# MIXR_Processing_-_STM32_DSP_Microcontrol.net
KiCad netlist of a schematic drawn in Altium Designer
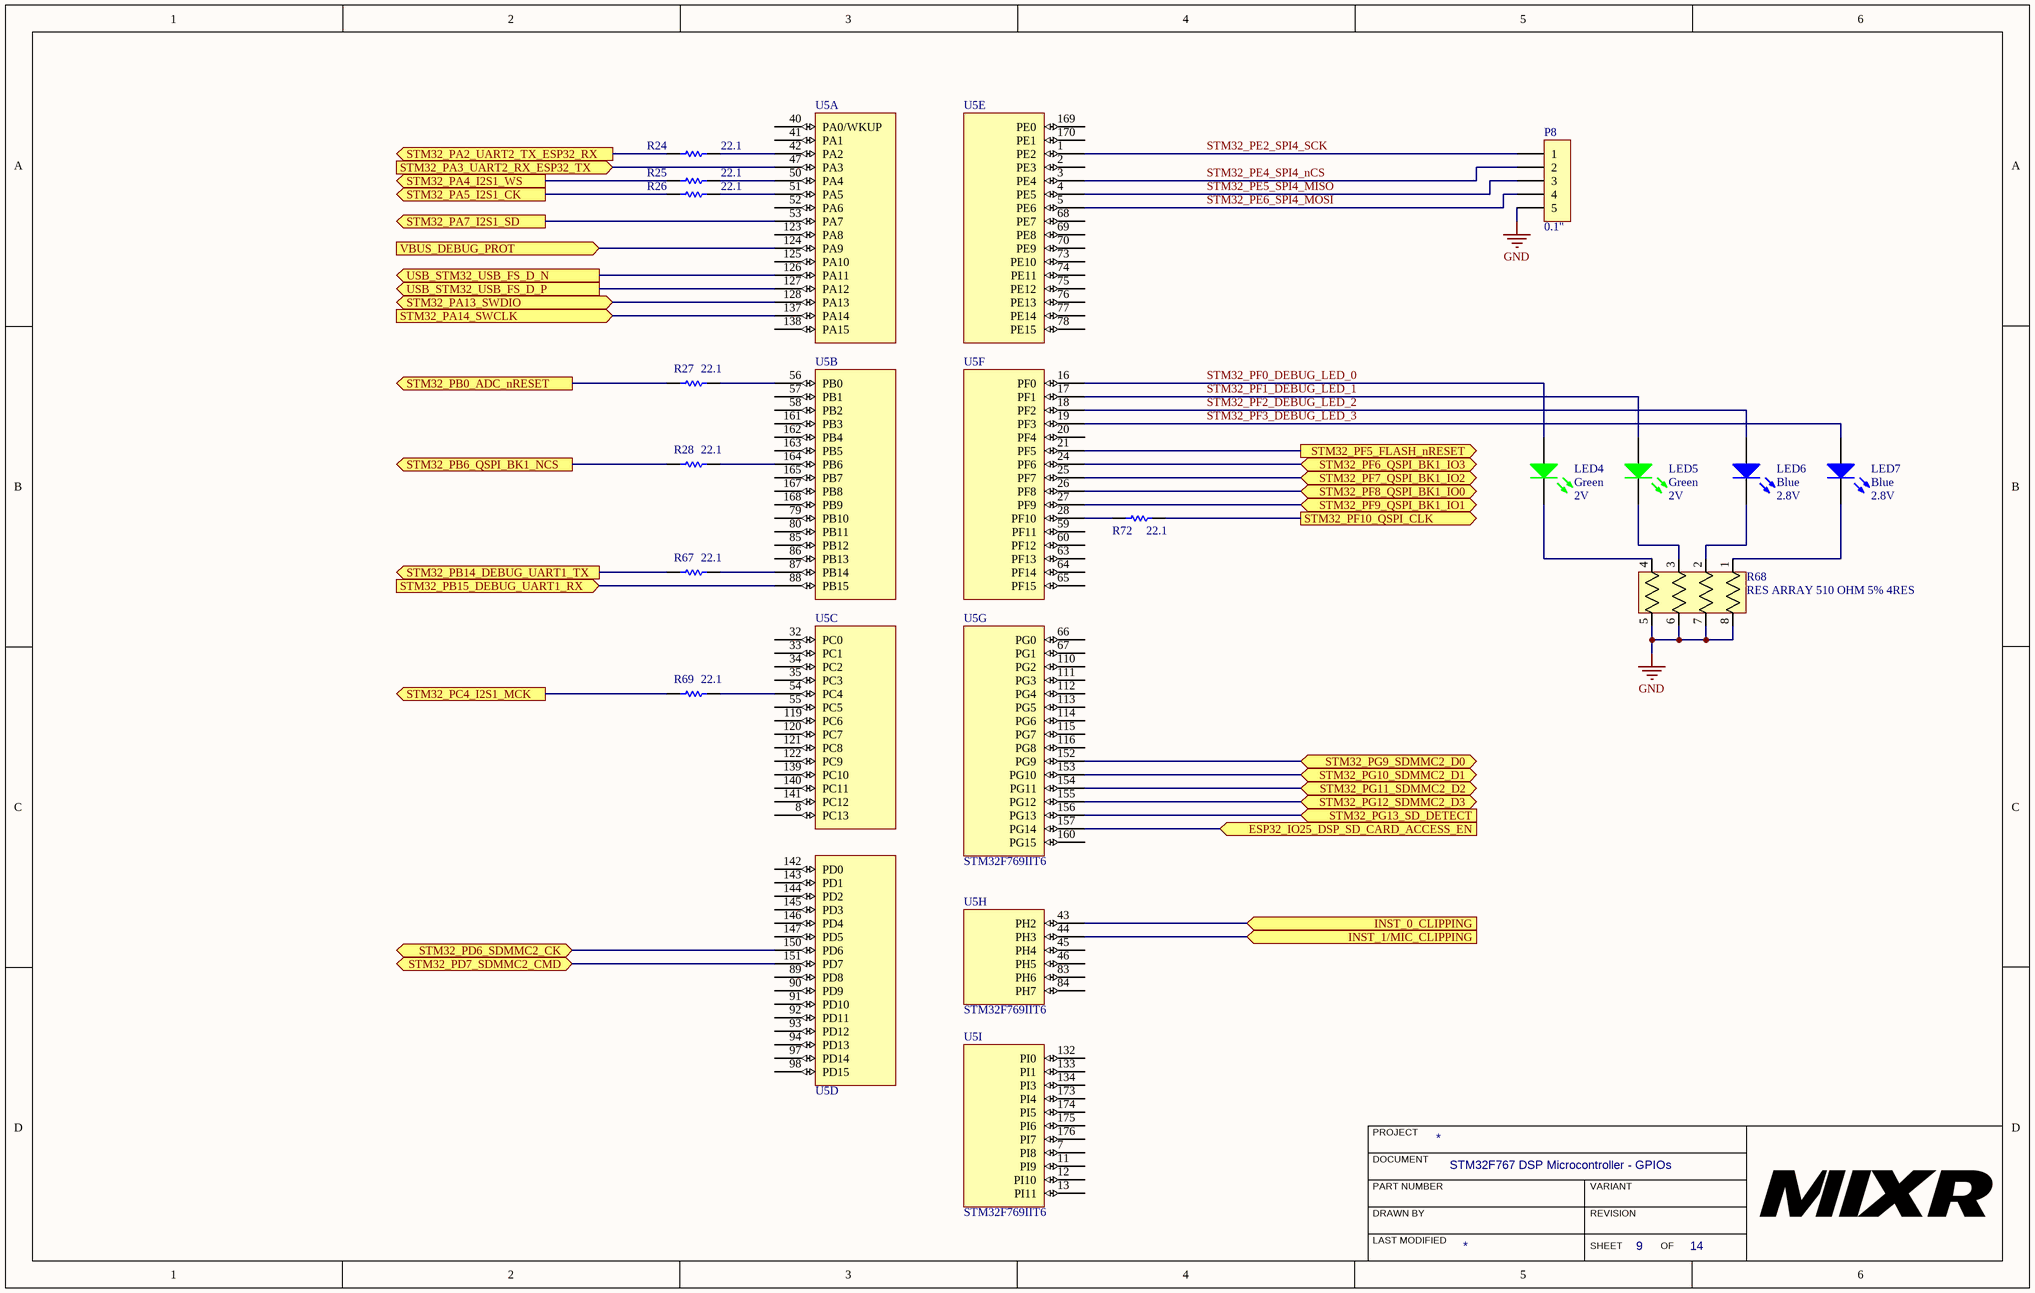
[diagram p0: MIXR Processing - STM32 DSP Microcontroller.SchDoc]

(export (version "E")
  (design (tool "Eeschema 10.0.6"))
  (components
    (comp (ref "LED4")
      (value "LED GREEN CLEAR 2V 0603")
      (footprint "LED_0603")
      (description "Green 572nm LED Indication - Discrete 2V 0603 (1608 Metric)")
      (fields
        (field (name "MANUFACTURER") "Wurth Electronics Inc.")
        (field (name "MANUFACTURER PART NUMBER") "150060VS75000")
        (field (name "COLOR") "Green")
        (field (name "VOLTAGE - FORWARD (VF) (TYP)") "2V")
      )
      (libsource (lib "Schematic Diagrams") (part "LED GREEN CLEAR 2V 0603"))
    )
    (comp (ref "LED5")
      (value "LED GREEN CLEAR 2V 0603")
      (footprint "LED_0603")
      (description "Green 572nm LED Indication - Discrete 2V 0603 (1608 Metric)")
      (fields
        (field (name "MANUFACTURER") "Wurth Electronics Inc.")
        (field (name "MANUFACTURER PART NUMBER") "150060VS75000")
        (field (name "COLOR") "Green")
        (field (name "VOLTAGE - FORWARD (VF) (TYP)") "2V")
      )
      (libsource (lib "Schematic Diagrams") (part "LED GREEN CLEAR 2V 0603"))
    )
    (comp (ref "LED6")
      (value "LED BLUE CLEAR 2.8V 0603")
      (footprint "LED_0603")
      (description "Blue 470nm LED Indication - Discrete 2.8V 0603 (1608 Metric)")
      (fields (field (name "COLOR") "Blue") (field (name "VOLTAGE - FORWARD (VF) (TYP)") "2.8V"))
      (libsource (lib "Schematic Diagrams") (part "LED BLUE CLEAR 2.8V 0603"))
    )
    (comp (ref "LED7")
      (value "LED BLUE CLEAR 2.8V 0603")
      (footprint "LED_0603")
      (description "Blue 470nm LED Indication - Discrete 2.8V 0603 (1608 Metric)")
      (fields (field (name "COLOR") "Blue") (field (name "VOLTAGE - FORWARD (VF) (TYP)") "2.8V"))
      (libsource (lib "Schematic Diagrams") (part "LED BLUE CLEAR 2.8V 0603"))
    )
    (comp (ref "P8")
      (value "0.1\"")
      (footprint "CONN, 5POS 1.23\" 0.100\" MALE Header")
      (description "CONN HEADER 5POS .100\" SNGL")
      (fields
        (field (name "MANUFACTURER") "Samtec")
        (field (name "MANUFACTURER PART NUMBER") "TSW-105-20-T-S")
      )
      (libsource (lib "Schematic Diagrams") (part "CONN 5POS 0.1{dblquote} 1{dblquote} MALE HEADER"))
    )
    (comp (ref "R24")
      (value "RES 22.1 OHM 1% 1/10W 0603")
      (footprint "RES, 0603")
      (description "22.1 Ohm ±1% 0.1W, 1/10W Chip Resistor 0603 (1608 Metric) Moisture Resistant Thick Film")
      (fields
        (field (name "TOLERANCE") "±1%")
        (field (name "RESISTANCE") "22.1")
        (field (name "POWER") "1/10W")
      )
      (libsource (lib "Schematic Diagrams") (part "RES 22.1 OHM 1% 1/10W 0603"))
    )
    (comp (ref "R25")
      (value "RES 22.1 OHM 1% 1/10W 0603")
      (footprint "RES, 0603")
      (description "22.1 Ohm ±1% 0.1W, 1/10W Chip Resistor 0603 (1608 Metric) Moisture Resistant Thick Film")
      (fields
        (field (name "TOLERANCE") "±1%")
        (field (name "RESISTANCE") "22.1")
        (field (name "POWER") "1/10W")
      )
      (libsource (lib "Schematic Diagrams") (part "RES 22.1 OHM 1% 1/10W 0603"))
    )
    (comp (ref "R26")
      (value "RES 22.1 OHM 1% 1/10W 0603")
      (footprint "RES, 0603")
      (description "22.1 Ohm ±1% 0.1W, 1/10W Chip Resistor 0603 (1608 Metric) Moisture Resistant Thick Film")
      (fields
        (field (name "TOLERANCE") "±1%")
        (field (name "RESISTANCE") "22.1")
        (field (name "POWER") "1/10W")
      )
      (libsource (lib "Schematic Diagrams") (part "RES 22.1 OHM 1% 1/10W 0603"))
    )
    (comp (ref "R27")
      (value "RES 22.1 OHM 1% 1/10W 0603")
      (footprint "RES, 0603")
      (description "22.1 Ohm ±1% 0.1W, 1/10W Chip Resistor 0603 (1608 Metric) Moisture Resistant Thick Film")
      (fields
        (field (name "TOLERANCE") "±1%")
        (field (name "RESISTANCE") "22.1")
        (field (name "POWER") "1/10W")
      )
      (libsource (lib "Schematic Diagrams") (part "RES 22.1 OHM 1% 1/10W 0603"))
    )
    (comp (ref "R28")
      (value "RES 22.1 OHM 1% 1/10W 0603")
      (footprint "RES, 0603")
      (description "22.1 Ohm ±1% 0.1W, 1/10W Chip Resistor 0603 (1608 Metric) Moisture Resistant Thick Film")
      (fields
        (field (name "TOLERANCE") "±1%")
        (field (name "RESISTANCE") "22.1")
        (field (name "POWER") "1/10W")
      )
      (libsource (lib "Schematic Diagrams") (part "RES 22.1 OHM 1% 1/10W 0603"))
    )
    (comp (ref "R67")
      (value "RES 22.1 OHM 1% 1/10W 0603")
      (footprint "RES, 0603")
      (description "22.1 Ohm ±1% 0.1W, 1/10W Chip Resistor 0603 (1608 Metric) Moisture Resistant Thick Film")
      (fields
        (field (name "TOLERANCE") "±1%")
        (field (name "RESISTANCE") "22.1")
        (field (name "POWER") "1/10W")
      )
      (libsource (lib "Schematic Diagrams") (part "RES 22.1 OHM 1% 1/10W 0603"))
    )
    (comp (ref "R68")
      (value "RES ARRAY 510 OHM 5% 4RES")
      (footprint "RES ARRAY 4 POS 0804")
      (description "RES ARRAY SMD 510 OHM 5% 4RES EXB-N8V511JX")
      (fields
        (field (name "MANUFACTURER") "Panasonic Electronic Components")
        (field (name "MANUFACTURER PART NUMBER") "EXB-N8V511JX")
      )
      (libsource (lib "Schematic Diagrams") (part "RES ARRAY 510 OHM 5% 4RES EXB-N8V511JX"))
    )
    (comp (ref "R69")
      (value "RES 22.1 OHM 1% 1/10W 0603")
      (footprint "RES, 0603")
      (description "22.1 Ohm ±1% 0.1W, 1/10W Chip Resistor 0603 (1608 Metric) Moisture Resistant Thick Film")
      (fields
        (field (name "TOLERANCE") "±1%")
        (field (name "RESISTANCE") "22.1")
        (field (name "POWER") "1/10W")
      )
      (libsource (lib "Schematic Diagrams") (part "RES 22.1 OHM 1% 1/10W 0603"))
    )
    (comp (ref "R72")
      (value "RES 22.1 OHM 1% 1/10W 0603")
      (footprint "RES, 0603")
      (description "22.1 Ohm ±1% 0.1W, 1/10W Chip Resistor 0603 (1608 Metric) Moisture Resistant Thick Film")
      (fields
        (field (name "TOLERANCE") "±1%")
        (field (name "RESISTANCE") "22.1")
        (field (name "POWER") "1/10W")
      )
      (libsource (lib "Schematic Diagrams") (part "RES 22.1 OHM 1% 1/10W 0603"))
    )
    (comp (ref "U5")
      (value "IC MCU STM32F769II 176-LQFP")
      (footprint "TSQFP50P2600X2600X160-176M")
      (description "ARM® Cortex®-M7 STM32F7 Microcontroller IC 32-Bit 216MHz 2MB (2M x 8) FLASH 176-LQFP (24x24)")
      (fields
        (field (name "MANUFACTURER") "STMicroelectronics")
        (field (name "MANUFACTURER PART NUMBER") "STM32F769IIT6")
      )
      (libsource (lib "") (part "IC MCU STM32F769II 176-LQFP_1"))
    )
  )
  (nets
    (net (code "1") (name "/ESP32_IO25_DSP_SD_CARD_ACCESS_EN") (class "Default")
      (node (ref "U5") (pin "157") (pinfunction "PG14_157") (pintype "bidirectional"))
    )
    (net (code "2") (name "/INST_0_CLIPPING") (class "Default")
      (node (ref "U5") (pin "43") (pinfunction "PH2_43") (pintype "bidirectional"))
    )
    (net (code "3") (name "/INST_1{slash}MIC_CLIPPING") (class "Default")
      (node (ref "U5") (pin "44") (pinfunction "PH3_44") (pintype "bidirectional"))
    )
    (net (code "4") (name "/STM32_PA2_UART2_TX_ESP32_RX") (class "Default")
      (node (ref "R24") (pin "1") (pinfunction "1_1") (pintype "passive"))
    )
    (net (code "5") (name "/STM32_PA3_UART2_RX_ESP32_TX") (class "Default")
      (node (ref "U5") (pin "47") (pinfunction "PA3_47") (pintype "bidirectional"))
    )
    (net (code "6") (name "/STM32_PA4_I2S1_WS") (class "Default")
      (node (ref "R25") (pin "1") (pinfunction "1_1") (pintype "passive"))
    )
    (net (code "7") (name "/STM32_PA5_I2S1_CK") (class "Default")
      (node (ref "R26") (pin "1") (pinfunction "1_1") (pintype "passive"))
    )
    (net (code "8") (name "/STM32_PA7_I2S1_SD") (class "Default")
      (node (ref "U5") (pin "53") (pinfunction "PA7_53") (pintype "bidirectional"))
    )
    (net (code "9") (name "/STM32_PA13_SWDIO") (class "Default")
      (node (ref "U5") (pin "128") (pinfunction "PA13_128") (pintype "bidirectional"))
    )
    (net (code "10") (name "/STM32_PA14_SWCLK") (class "Default")
      (node (ref "U5") (pin "137") (pinfunction "PA14_137") (pintype "bidirectional"))
    )
    (net (code "11") (name "/STM32_PB0_ADC_nRESET") (class "Default")
      (node (ref "R27") (pin "1") (pinfunction "1_1") (pintype "passive"))
    )
    (net (code "12") (name "/STM32_PB6_QSPI_BK1_NCS") (class "Default")
      (node (ref "R28") (pin "1") (pinfunction "1_1") (pintype "passive"))
    )
    (net (code "13") (name "/STM32_PB14_DEBUG_UART1_TX") (class "Default")
      (node (ref "R67") (pin "1") (pinfunction "1_1") (pintype "passive"))
    )
    (net (code "14") (name "/STM32_PB15_DEBUG_UART1_RX") (class "Default")
      (node (ref "U5") (pin "88") (pinfunction "PB15_88") (pintype "bidirectional"))
    )
    (net (code "15") (name "/STM32_PC4_I2S1_MCK") (class "Default")
      (node (ref "R69") (pin "1") (pinfunction "1_1") (pintype "passive"))
    )
    (net (code "16") (name "/STM32_PD6_SDMMC2_CK") (class "Default")
      (node (ref "U5") (pin "150") (pinfunction "PD6_150") (pintype "bidirectional"))
    )
    (net (code "17") (name "/STM32_PD7_SDMMC2_CMD") (class "Default")
      (node (ref "U5") (pin "151") (pinfunction "PD7_151") (pintype "bidirectional"))
    )
    (net (code "18") (name "/STM32_PE2_SPI4_SCK") (class "Default")
      (node (ref "P8") (pin "1") (pinfunction "1_1") (pintype "passive"))
      (node (ref "U5") (pin "1") (pinfunction "PE2_1") (pintype "bidirectional"))
    )
    (net (code "19") (name "/STM32_PE4_SPI4_nCS") (class "Default")
      (node (ref "P8") (pin "2") (pinfunction "2_2") (pintype "passive"))
      (node (ref "U5") (pin "3") (pinfunction "PE4_3") (pintype "bidirectional"))
    )
    (net (code "20") (name "/STM32_PE5_SPI4_MISO") (class "Default")
      (node (ref "P8") (pin "3") (pinfunction "3_3") (pintype "passive"))
      (node (ref "U5") (pin "4") (pinfunction "PE5_4") (pintype "bidirectional"))
    )
    (net (code "21") (name "/STM32_PE6_SPI4_MOSI") (class "Default")
      (node (ref "P8") (pin "4") (pinfunction "4_4") (pintype "passive"))
      (node (ref "U5") (pin "5") (pinfunction "PE6_5") (pintype "bidirectional"))
    )
    (net (code "22") (name "/STM32_PF0_DEBUG_LED_0") (class "Default")
      (node (ref "LED4") (pin "1") (pinfunction "A_1") (pintype "passive"))
      (node (ref "U5") (pin "16") (pinfunction "PF0_16") (pintype "bidirectional"))
    )
    (net (code "23") (name "/STM32_PF1_DEBUG_LED_1") (class "Default")
      (node (ref "LED5") (pin "1") (pinfunction "A_1") (pintype "passive"))
      (node (ref "U5") (pin "17") (pinfunction "PF1_17") (pintype "bidirectional"))
    )
    (net (code "24") (name "/STM32_PF2_DEBUG_LED_2") (class "Default")
      (node (ref "LED6") (pin "1") (pinfunction "A_1") (pintype "passive"))
      (node (ref "U5") (pin "18") (pinfunction "PF2_18") (pintype "bidirectional"))
    )
    (net (code "25") (name "/STM32_PF3_DEBUG_LED_3") (class "Default")
      (node (ref "LED7") (pin "1") (pinfunction "A_1") (pintype "passive"))
      (node (ref "U5") (pin "19") (pinfunction "PF3_19") (pintype "bidirectional"))
    )
    (net (code "26") (name "/STM32_PF5_FLASH_nRESET") (class "Default")
      (node (ref "U5") (pin "21") (pinfunction "PF5_21") (pintype "bidirectional"))
    )
    (net (code "27") (name "/STM32_PF6_QSPI_BK1_IO3") (class "Default")
      (node (ref "U5") (pin "24") (pinfunction "PF6_24") (pintype "bidirectional"))
    )
    (net (code "28") (name "/STM32_PF7_QSPI_BK1_IO2") (class "Default")
      (node (ref "U5") (pin "25") (pinfunction "PF7_25") (pintype "bidirectional"))
    )
    (net (code "29") (name "/STM32_PF8_QSPI_BK1_IO0") (class "Default")
      (node (ref "U5") (pin "26") (pinfunction "PF8_26") (pintype "bidirectional"))
    )
    (net (code "30") (name "/STM32_PF9_QSPI_BK1_IO1") (class "Default")
      (node (ref "U5") (pin "27") (pinfunction "PF9_27") (pintype "bidirectional"))
    )
    (net (code "31") (name "/STM32_PF10_QSPI_CLK") (class "Default")
      (node (ref "R72") (pin "2") (pinfunction "2_2") (pintype "passive"))
    )
    (net (code "32") (name "/STM32_PG9_SDMMC2_D0") (class "Default")
      (node (ref "U5") (pin "152") (pinfunction "PG9_152") (pintype "bidirectional"))
    )
    (net (code "33") (name "/STM32_PG10_SDMMC2_D1") (class "Default")
      (node (ref "U5") (pin "153") (pinfunction "PG10_153") (pintype "bidirectional"))
    )
    (net (code "34") (name "/STM32_PG11_SDMMC2_D2") (class "Default")
      (node (ref "U5") (pin "154") (pinfunction "PG11_154") (pintype "bidirectional"))
    )
    (net (code "35") (name "/STM32_PG12_SDMMC2_D3") (class "Default")
      (node (ref "U5") (pin "155") (pinfunction "PG12_155") (pintype "bidirectional"))
    )
    (net (code "36") (name "/STM32_PG13_SD_DETECT") (class "Default")
      (node (ref "U5") (pin "156") (pinfunction "PG13_156") (pintype "bidirectional"))
    )
    (net (code "37") (name "/USB_STM32_USB_FS_D_N") (class "Default")
      (node (ref "U5") (pin "126") (pinfunction "PA11_126") (pintype "bidirectional"))
    )
    (net (code "38") (name "/USB_STM32_USB_FS_D_P") (class "Default")
      (node (ref "U5") (pin "127") (pinfunction "PA12_127") (pintype "bidirectional"))
    )
    (net (code "39") (name "/VBUS_DEBUG_PROT") (class "Default")
      (node (ref "U5") (pin "124") (pinfunction "PA9_124") (pintype "bidirectional"))
    )
    (net (code "40") (name "GND") (class "Default")
      (node (ref "P8") (pin "5") (pinfunction "5_5") (pintype "passive"))
      (node (ref "R68") (pin "5") (pinfunction "5_5") (pintype "passive"))
      (node (ref "R68") (pin "6") (pinfunction "6_6") (pintype "passive"))
      (node (ref "R68") (pin "7") (pinfunction "7_7") (pintype "passive"))
      (node (ref "R68") (pin "8") (pinfunction "8_8") (pintype "passive"))
    )
    (net (code "41") (name "Net-(LED4-K)") (class "Default")
      (node (ref "LED4") (pin "2") (pinfunction "K_2") (pintype "passive"))
      (node (ref "R68") (pin "4") (pinfunction "4_4") (pintype "passive"))
    )
    (net (code "42") (name "Net-(LED5-K)") (class "Default")
      (node (ref "LED5") (pin "2") (pinfunction "K_2") (pintype "passive"))
      (node (ref "R68") (pin "3") (pinfunction "3_3") (pintype "passive"))
    )
    (net (code "43") (name "Net-(LED6-K)") (class "Default")
      (node (ref "LED6") (pin "2") (pinfunction "K_2") (pintype "passive"))
      (node (ref "R68") (pin "2") (pinfunction "2_2") (pintype "passive"))
    )
    (net (code "44") (name "Net-(LED7-K)") (class "Default")
      (node (ref "LED7") (pin "2") (pinfunction "K_2") (pintype "passive"))
      (node (ref "R68") (pin "1") (pinfunction "1_1") (pintype "passive"))
    )
    (net (code "45") (name "Net-(U5A-PA2)") (class "Default")
      (node (ref "R24") (pin "2") (pinfunction "2_2") (pintype "passive"))
      (node (ref "U5") (pin "42") (pinfunction "PA2_42") (pintype "bidirectional"))
    )
    (net (code "46") (name "Net-(U5A-PA4)") (class "Default")
      (node (ref "R25") (pin "2") (pinfunction "2_2") (pintype "passive"))
      (node (ref "U5") (pin "50") (pinfunction "PA4_50") (pintype "bidirectional"))
    )
    (net (code "47") (name "Net-(U5A-PA5)") (class "Default")
      (node (ref "R26") (pin "2") (pinfunction "2_2") (pintype "passive"))
      (node (ref "U5") (pin "51") (pinfunction "PA5_51") (pintype "bidirectional"))
    )
    (net (code "48") (name "Net-(U5B-PB0)") (class "Default")
      (node (ref "R27") (pin "2") (pinfunction "2_2") (pintype "passive"))
      (node (ref "U5") (pin "56") (pinfunction "PB0_56") (pintype "bidirectional"))
    )
    (net (code "49") (name "Net-(U5B-PB6)") (class "Default")
      (node (ref "R28") (pin "2") (pinfunction "2_2") (pintype "passive"))
      (node (ref "U5") (pin "164") (pinfunction "PB6_164") (pintype "bidirectional"))
    )
    (net (code "50") (name "Net-(U5B-PB14)") (class "Default")
      (node (ref "R67") (pin "2") (pinfunction "2_2") (pintype "passive"))
      (node (ref "U5") (pin "87") (pinfunction "PB14_87") (pintype "bidirectional"))
    )
    (net (code "51") (name "Net-(U5C-PC4)") (class "Default")
      (node (ref "R69") (pin "2") (pinfunction "2_2") (pintype "passive"))
      (node (ref "U5") (pin "54") (pinfunction "PC4_54") (pintype "bidirectional"))
    )
    (net (code "52") (name "Net-(U5F-PF10)") (class "Default")
      (node (ref "R72") (pin "1") (pinfunction "1_1") (pintype "passive"))
      (node (ref "U5") (pin "28") (pinfunction "PF10_28") (pintype "bidirectional"))
    )
    (net (code "53") (name "unconnected-(U5A-PA0{slash}WKUP-Pad40)") (class "Default")
      (node (ref "U5") (pin "40") (pinfunction "PA0/WKUP_40") (pintype "bidirectional"))
    )
    (net (code "54") (name "unconnected-(U5A-PA1-Pad41)") (class "Default")
      (node (ref "U5") (pin "41") (pinfunction "PA1_41") (pintype "bidirectional"))
    )
    (net (code "55") (name "unconnected-(U5A-PA6-Pad52)") (class "Default")
      (node (ref "U5") (pin "52") (pinfunction "PA6_52") (pintype "bidirectional"))
    )
    (net (code "56") (name "unconnected-(U5A-PA8-Pad123)") (class "Default")
      (node (ref "U5") (pin "123") (pinfunction "PA8_123") (pintype "bidirectional"))
    )
    (net (code "57") (name "unconnected-(U5A-PA10-Pad125)") (class "Default")
      (node (ref "U5") (pin "125") (pinfunction "PA10_125") (pintype "bidirectional"))
    )
    (net (code "58") (name "unconnected-(U5A-PA15-Pad138)") (class "Default")
      (node (ref "U5") (pin "138") (pinfunction "PA15_138") (pintype "bidirectional"))
    )
    (net (code "59") (name "unconnected-(U5B-PB1-Pad57)") (class "Default")
      (node (ref "U5") (pin "57") (pinfunction "PB1_57") (pintype "bidirectional"))
    )
    (net (code "60") (name "unconnected-(U5B-PB2-Pad58)") (class "Default")
      (node (ref "U5") (pin "58") (pinfunction "PB2_58") (pintype "bidirectional"))
    )
    (net (code "61") (name "unconnected-(U5B-PB3-Pad161)") (class "Default")
      (node (ref "U5") (pin "161") (pinfunction "PB3_161") (pintype "bidirectional"))
    )
    (net (code "62") (name "unconnected-(U5B-PB4-Pad162)") (class "Default")
      (node (ref "U5") (pin "162") (pinfunction "PB4_162") (pintype "bidirectional"))
    )
    (net (code "63") (name "unconnected-(U5B-PB5-Pad163)") (class "Default")
      (node (ref "U5") (pin "163") (pinfunction "PB5_163") (pintype "bidirectional"))
    )
    (net (code "64") (name "unconnected-(U5B-PB7-Pad165)") (class "Default")
      (node (ref "U5") (pin "165") (pinfunction "PB7_165") (pintype "bidirectional"))
    )
    (net (code "65") (name "unconnected-(U5B-PB8-Pad167)") (class "Default")
      (node (ref "U5") (pin "167") (pinfunction "PB8_167") (pintype "bidirectional"))
    )
    (net (code "66") (name "unconnected-(U5B-PB9-Pad168)") (class "Default")
      (node (ref "U5") (pin "168") (pinfunction "PB9_168") (pintype "bidirectional"))
    )
    (net (code "67") (name "unconnected-(U5B-PB10-Pad79)") (class "Default")
      (node (ref "U5") (pin "79") (pinfunction "PB10_79") (pintype "bidirectional"))
    )
    (net (code "68") (name "unconnected-(U5B-PB11-Pad80)") (class "Default")
      (node (ref "U5") (pin "80") (pinfunction "PB11_80") (pintype "bidirectional"))
    )
    (net (code "69") (name "unconnected-(U5B-PB12-Pad85)") (class "Default")
      (node (ref "U5") (pin "85") (pinfunction "PB12_85") (pintype "bidirectional"))
    )
    (net (code "70") (name "unconnected-(U5B-PB13-Pad86)") (class "Default")
      (node (ref "U5") (pin "86") (pinfunction "PB13_86") (pintype "bidirectional"))
    )
    (net (code "71") (name "unconnected-(U5C-PC0-Pad32)") (class "Default")
      (node (ref "U5") (pin "32") (pinfunction "PC0_32") (pintype "bidirectional"))
    )
    (net (code "72") (name "unconnected-(U5C-PC1-Pad33)") (class "Default")
      (node (ref "U5") (pin "33") (pinfunction "PC1_33") (pintype "bidirectional"))
    )
    (net (code "73") (name "unconnected-(U5C-PC2-Pad34)") (class "Default")
      (node (ref "U5") (pin "34") (pinfunction "PC2_34") (pintype "bidirectional"))
    )
    (net (code "74") (name "unconnected-(U5C-PC3-Pad35)") (class "Default")
      (node (ref "U5") (pin "35") (pinfunction "PC3_35") (pintype "bidirectional"))
    )
    (net (code "75") (name "unconnected-(U5C-PC5-Pad55)") (class "Default")
      (node (ref "U5") (pin "55") (pinfunction "PC5_55") (pintype "bidirectional"))
    )
    (net (code "76") (name "unconnected-(U5C-PC6-Pad119)") (class "Default")
      (node (ref "U5") (pin "119") (pinfunction "PC6_119") (pintype "bidirectional"))
    )
    (net (code "77") (name "unconnected-(U5C-PC7-Pad120)") (class "Default")
      (node (ref "U5") (pin "120") (pinfunction "PC7_120") (pintype "bidirectional"))
    )
    (net (code "78") (name "unconnected-(U5C-PC8-Pad121)") (class "Default")
      (node (ref "U5") (pin "121") (pinfunction "PC8_121") (pintype "bidirectional"))
    )
    (net (code "79") (name "unconnected-(U5C-PC9-Pad122)") (class "Default")
      (node (ref "U5") (pin "122") (pinfunction "PC9_122") (pintype "bidirectional"))
    )
    (net (code "80") (name "unconnected-(U5C-PC10-Pad139)") (class "Default")
      (node (ref "U5") (pin "139") (pinfunction "PC10_139") (pintype "bidirectional"))
    )
    (net (code "81") (name "unconnected-(U5C-PC11-Pad140)") (class "Default")
      (node (ref "U5") (pin "140") (pinfunction "PC11_140") (pintype "bidirectional"))
    )
    (net (code "82") (name "unconnected-(U5C-PC12-Pad141)") (class "Default")
      (node (ref "U5") (pin "141") (pinfunction "PC12_141") (pintype "bidirectional"))
    )
    (net (code "83") (name "unconnected-(U5C-PC13-Pad8)") (class "Default")
      (node (ref "U5") (pin "8") (pinfunction "PC13_8") (pintype "bidirectional"))
    )
    (net (code "84") (name "unconnected-(U5D-PD0-Pad142)") (class "Default")
      (node (ref "U5") (pin "142") (pinfunction "PD0_142") (pintype "bidirectional"))
    )
    (net (code "85") (name "unconnected-(U5D-PD1-Pad143)") (class "Default")
      (node (ref "U5") (pin "143") (pinfunction "PD1_143") (pintype "bidirectional"))
    )
    (net (code "86") (name "unconnected-(U5D-PD2-Pad144)") (class "Default")
      (node (ref "U5") (pin "144") (pinfunction "PD2_144") (pintype "bidirectional"))
    )
    (net (code "87") (name "unconnected-(U5D-PD3-Pad145)") (class "Default")
      (node (ref "U5") (pin "145") (pinfunction "PD3_145") (pintype "bidirectional"))
    )
    (net (code "88") (name "unconnected-(U5D-PD4-Pad146)") (class "Default")
      (node (ref "U5") (pin "146") (pinfunction "PD4_146") (pintype "bidirectional"))
    )
    (net (code "89") (name "unconnected-(U5D-PD5-Pad147)") (class "Default")
      (node (ref "U5") (pin "147") (pinfunction "PD5_147") (pintype "bidirectional"))
    )
    (net (code "90") (name "unconnected-(U5D-PD8-Pad89)") (class "Default")
      (node (ref "U5") (pin "89") (pinfunction "PD8_89") (pintype "bidirectional"))
    )
    (net (code "91") (name "unconnected-(U5D-PD9-Pad90)") (class "Default")
      (node (ref "U5") (pin "90") (pinfunction "PD9_90") (pintype "bidirectional"))
    )
    (net (code "92") (name "unconnected-(U5D-PD10-Pad91)") (class "Default")
      (node (ref "U5") (pin "91") (pinfunction "PD10_91") (pintype "bidirectional"))
    )
    (net (code "93") (name "unconnected-(U5D-PD11-Pad92)") (class "Default")
      (node (ref "U5") (pin "92") (pinfunction "PD11_92") (pintype "bidirectional"))
    )
    (net (code "94") (name "unconnected-(U5D-PD12-Pad93)") (class "Default")
      (node (ref "U5") (pin "93") (pinfunction "PD12_93") (pintype "bidirectional"))
    )
    (net (code "95") (name "unconnected-(U5D-PD13-Pad94)") (class "Default")
      (node (ref "U5") (pin "94") (pinfunction "PD13_94") (pintype "bidirectional"))
    )
    (net (code "96") (name "unconnected-(U5D-PD14-Pad97)") (class "Default")
      (node (ref "U5") (pin "97") (pinfunction "PD14_97") (pintype "bidirectional"))
    )
    (net (code "97") (name "unconnected-(U5D-PD15-Pad98)") (class "Default")
      (node (ref "U5") (pin "98") (pinfunction "PD15_98") (pintype "bidirectional"))
    )
    (net (code "98") (name "unconnected-(U5E-PE0-Pad169)") (class "Default")
      (node (ref "U5") (pin "169") (pinfunction "PE0_169") (pintype "bidirectional"))
    )
    (net (code "99") (name "unconnected-(U5E-PE1-Pad170)") (class "Default")
      (node (ref "U5") (pin "170") (pinfunction "PE1_170") (pintype "bidirectional"))
    )
    (net (code "100") (name "unconnected-(U5E-PE3-Pad2)") (class "Default")
      (node (ref "U5") (pin "2") (pinfunction "PE3_2") (pintype "bidirectional"))
    )
    (net (code "101") (name "unconnected-(U5E-PE7-Pad68)") (class "Default")
      (node (ref "U5") (pin "68") (pinfunction "PE7_68") (pintype "bidirectional"))
    )
    (net (code "102") (name "unconnected-(U5E-PE8-Pad69)") (class "Default")
      (node (ref "U5") (pin "69") (pinfunction "PE8_69") (pintype "bidirectional"))
    )
    (net (code "103") (name "unconnected-(U5E-PE9-Pad70)") (class "Default")
      (node (ref "U5") (pin "70") (pinfunction "PE9_70") (pintype "bidirectional"))
    )
    (net (code "104") (name "unconnected-(U5E-PE10-Pad73)") (class "Default")
      (node (ref "U5") (pin "73") (pinfunction "PE10_73") (pintype "bidirectional"))
    )
    (net (code "105") (name "unconnected-(U5E-PE11-Pad74)") (class "Default")
      (node (ref "U5") (pin "74") (pinfunction "PE11_74") (pintype "bidirectional"))
    )
    (net (code "106") (name "unconnected-(U5E-PE12-Pad75)") (class "Default")
      (node (ref "U5") (pin "75") (pinfunction "PE12_75") (pintype "bidirectional"))
    )
    (net (code "107") (name "unconnected-(U5E-PE13-Pad76)") (class "Default")
      (node (ref "U5") (pin "76") (pinfunction "PE13_76") (pintype "bidirectional"))
    )
    (net (code "108") (name "unconnected-(U5E-PE14-Pad77)") (class "Default")
      (node (ref "U5") (pin "77") (pinfunction "PE14_77") (pintype "bidirectional"))
    )
    (net (code "109") (name "unconnected-(U5E-PE15-Pad78)") (class "Default")
      (node (ref "U5") (pin "78") (pinfunction "PE15_78") (pintype "bidirectional"))
    )
    (net (code "110") (name "unconnected-(U5F-PF4-Pad20)") (class "Default")
      (node (ref "U5") (pin "20") (pinfunction "PF4_20") (pintype "bidirectional"))
    )
    (net (code "111") (name "unconnected-(U5F-PF11-Pad59)") (class "Default")
      (node (ref "U5") (pin "59") (pinfunction "PF11_59") (pintype "bidirectional"))
    )
    (net (code "112") (name "unconnected-(U5F-PF12-Pad60)") (class "Default")
      (node (ref "U5") (pin "60") (pinfunction "PF12_60") (pintype "bidirectional"))
    )
    (net (code "113") (name "unconnected-(U5F-PF13-Pad63)") (class "Default")
      (node (ref "U5") (pin "63") (pinfunction "PF13_63") (pintype "bidirectional"))
    )
    (net (code "114") (name "unconnected-(U5F-PF14-Pad64)") (class "Default")
      (node (ref "U5") (pin "64") (pinfunction "PF14_64") (pintype "bidirectional"))
    )
    (net (code "115") (name "unconnected-(U5F-PF15-Pad65)") (class "Default")
      (node (ref "U5") (pin "65") (pinfunction "PF15_65") (pintype "bidirectional"))
    )
    (net (code "116") (name "unconnected-(U5G-PG0-Pad66)") (class "Default")
      (node (ref "U5") (pin "66") (pinfunction "PG0_66") (pintype "bidirectional"))
    )
    (net (code "117") (name "unconnected-(U5G-PG1-Pad67)") (class "Default")
      (node (ref "U5") (pin "67") (pinfunction "PG1_67") (pintype "bidirectional"))
    )
    (net (code "118") (name "unconnected-(U5G-PG2-Pad110)") (class "Default")
      (node (ref "U5") (pin "110") (pinfunction "PG2_110") (pintype "bidirectional"))
    )
    (net (code "119") (name "unconnected-(U5G-PG3-Pad111)") (class "Default")
      (node (ref "U5") (pin "111") (pinfunction "PG3_111") (pintype "bidirectional"))
    )
    (net (code "120") (name "unconnected-(U5G-PG4-Pad112)") (class "Default")
      (node (ref "U5") (pin "112") (pinfunction "PG4_112") (pintype "bidirectional"))
    )
    (net (code "121") (name "unconnected-(U5G-PG5-Pad113)") (class "Default")
      (node (ref "U5") (pin "113") (pinfunction "PG5_113") (pintype "bidirectional"))
    )
    (net (code "122") (name "unconnected-(U5G-PG6-Pad114)") (class "Default")
      (node (ref "U5") (pin "114") (pinfunction "PG6_114") (pintype "bidirectional"))
    )
    (net (code "123") (name "unconnected-(U5G-PG7-Pad115)") (class "Default")
      (node (ref "U5") (pin "115") (pinfunction "PG7_115") (pintype "bidirectional"))
    )
    (net (code "124") (name "unconnected-(U5G-PG8-Pad116)") (class "Default")
      (node (ref "U5") (pin "116") (pinfunction "PG8_116") (pintype "bidirectional"))
    )
    (net (code "125") (name "unconnected-(U5G-PG15-Pad160)") (class "Default")
      (node (ref "U5") (pin "160") (pinfunction "PG15_160") (pintype "bidirectional"))
    )
    (net (code "126") (name "unconnected-(U5H-PH4-Pad45)") (class "Default")
      (node (ref "U5") (pin "45") (pinfunction "PH4_45") (pintype "bidirectional"))
    )
    (net (code "127") (name "unconnected-(U5H-PH5-Pad46)") (class "Default")
      (node (ref "U5") (pin "46") (pinfunction "PH5_46") (pintype "bidirectional"))
    )
    (net (code "128") (name "unconnected-(U5H-PH6-Pad83)") (class "Default")
      (node (ref "U5") (pin "83") (pinfunction "PH6_83") (pintype "bidirectional"))
    )
    (net (code "129") (name "unconnected-(U5H-PH7-Pad84)") (class "Default")
      (node (ref "U5") (pin "84") (pinfunction "PH7_84") (pintype "bidirectional"))
    )
    (net (code "130") (name "unconnected-(U5I-PI0-Pad132)") (class "Default")
      (node (ref "U5") (pin "132") (pinfunction "PI0_132") (pintype "bidirectional"))
    )
    (net (code "131") (name "unconnected-(U5I-PI1-Pad133)") (class "Default")
      (node (ref "U5") (pin "133") (pinfunction "PI1_133") (pintype "bidirectional"))
    )
    (net (code "132") (name "unconnected-(U5I-PI3-Pad134)") (class "Default")
      (node (ref "U5") (pin "134") (pinfunction "PI3_134") (pintype "bidirectional"))
    )
    (net (code "133") (name "unconnected-(U5I-PI4-Pad173)") (class "Default")
      (node (ref "U5") (pin "173") (pinfunction "PI4_173") (pintype "bidirectional"))
    )
    (net (code "134") (name "unconnected-(U5I-PI5-Pad174)") (class "Default")
      (node (ref "U5") (pin "174") (pinfunction "PI5_174") (pintype "bidirectional"))
    )
    (net (code "135") (name "unconnected-(U5I-PI6-Pad175)") (class "Default")
      (node (ref "U5") (pin "175") (pinfunction "PI6_175") (pintype "bidirectional"))
    )
    (net (code "136") (name "unconnected-(U5I-PI7-Pad176)") (class "Default")
      (node (ref "U5") (pin "176") (pinfunction "PI7_176") (pintype "bidirectional"))
    )
    (net (code "137") (name "unconnected-(U5I-PI8-Pad7)") (class "Default")
      (node (ref "U5") (pin "7") (pinfunction "PI8_7") (pintype "bidirectional"))
    )
    (net (code "138") (name "unconnected-(U5I-PI9-Pad11)") (class "Default")
      (node (ref "U5") (pin "11") (pinfunction "PI9_11") (pintype "bidirectional"))
    )
    (net (code "139") (name "unconnected-(U5I-PI10-Pad12)") (class "Default")
      (node (ref "U5") (pin "12") (pinfunction "PI10_12") (pintype "bidirectional"))
    )
    (net (code "140") (name "unconnected-(U5I-PI11-Pad13)") (class "Default")
      (node (ref "U5") (pin "13") (pinfunction "PI11_13") (pintype "bidirectional"))
    )
  )
)
